# ws2811.net
KiCad netlist of a schematic drawn in EAGLE
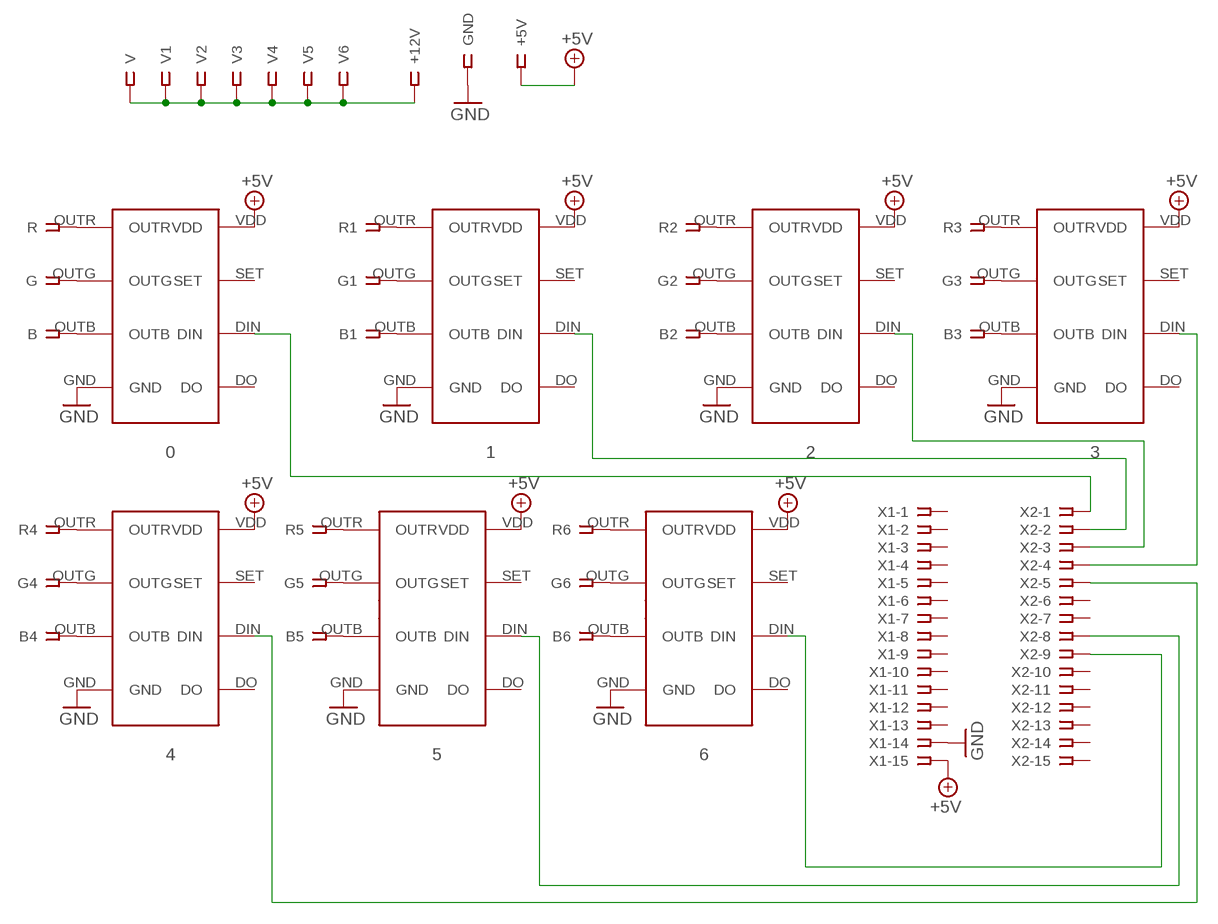
[diagram p0: schematic, sheet 1]

(export (version "E")
  (design (tool "Eeschema 10.0.6"))
  (components
    (comp (ref "+5V")
      (value "SSW-101-02-G-S")
      (footprint "eagle-import:SSW-101-02-G-S")
      (fields (field (name "MF") "Samtec Inc."))
      (libsource (lib "eagle-import") (part "SSW-101-02-G-S"))
    )
    (comp (ref "+12V")
      (value "SSW-101-02-G-S")
      (footprint "eagle-import:SSW-101-02-G-S")
      (fields (field (name "MF") "Samtec Inc."))
      (libsource (lib "eagle-import") (part "SSW-101-02-G-S"))
    )
    (comp (ref "0")
      (value "WS2811")
      (footprint "eagle-import:SOP8")
      (libsource (lib "eagle-import") (part "WS2811"))
    )
    (comp (ref "1")
      (value "WS2811")
      (footprint "eagle-import:SOP8")
      (libsource (lib "eagle-import") (part "WS2811"))
    )
    (comp (ref "2")
      (value "WS2811")
      (footprint "eagle-import:SOP8")
      (libsource (lib "eagle-import") (part "WS2811"))
    )
    (comp (ref "3")
      (value "WS2811")
      (footprint "eagle-import:SOP8")
      (libsource (lib "eagle-import") (part "WS2811"))
    )
    (comp (ref "4")
      (value "WS2811")
      (footprint "eagle-import:SOP8")
      (libsource (lib "eagle-import") (part "WS2811"))
    )
    (comp (ref "5")
      (value "WS2811")
      (footprint "eagle-import:SOP8")
      (libsource (lib "eagle-import") (part "WS2811"))
    )
    (comp (ref "6")
      (value "WS2811")
      (footprint "eagle-import:SOP8")
      (libsource (lib "eagle-import") (part "WS2811"))
    )
    (comp (ref "B")
      (value "SSW-101-02-G-S")
      (footprint "eagle-import:SSW-101-02-G-S")
      (fields (field (name "MF") "Samtec Inc."))
      (libsource (lib "eagle-import") (part "SSW-101-02-G-S"))
    )
    (comp (ref "B1")
      (value "SSW-101-02-G-S")
      (footprint "eagle-import:SSW-101-02-G-S")
      (fields (field (name "MF") "Samtec Inc."))
      (libsource (lib "eagle-import") (part "SSW-101-02-G-S"))
    )
    (comp (ref "B2")
      (value "SSW-101-02-G-S")
      (footprint "eagle-import:SSW-101-02-G-S")
      (fields (field (name "MF") "Samtec Inc."))
      (libsource (lib "eagle-import") (part "SSW-101-02-G-S"))
    )
    (comp (ref "B3")
      (value "SSW-101-02-G-S")
      (footprint "eagle-import:SSW-101-02-G-S")
      (fields (field (name "MF") "Samtec Inc."))
      (libsource (lib "eagle-import") (part "SSW-101-02-G-S"))
    )
    (comp (ref "B4")
      (value "SSW-101-02-G-S")
      (footprint "eagle-import:SSW-101-02-G-S")
      (fields (field (name "MF") "Samtec Inc."))
      (libsource (lib "eagle-import") (part "SSW-101-02-G-S"))
    )
    (comp (ref "B5")
      (value "SSW-101-02-G-S")
      (footprint "eagle-import:SSW-101-02-G-S")
      (fields (field (name "MF") "Samtec Inc."))
      (libsource (lib "eagle-import") (part "SSW-101-02-G-S"))
    )
    (comp (ref "B6")
      (value "SSW-101-02-G-S")
      (footprint "eagle-import:SSW-101-02-G-S")
      (fields (field (name "MF") "Samtec Inc."))
      (libsource (lib "eagle-import") (part "SSW-101-02-G-S"))
    )
    (comp (ref "G")
      (value "SSW-101-02-G-S")
      (footprint "eagle-import:SSW-101-02-G-S")
      (fields (field (name "MF") "Samtec Inc."))
      (libsource (lib "eagle-import") (part "SSW-101-02-G-S"))
    )
    (comp (ref "G1")
      (value "SSW-101-02-G-S")
      (footprint "eagle-import:SSW-101-02-G-S")
      (fields (field (name "MF") "Samtec Inc."))
      (libsource (lib "eagle-import") (part "SSW-101-02-G-S"))
    )
    (comp (ref "G2")
      (value "SSW-101-02-G-S")
      (footprint "eagle-import:SSW-101-02-G-S")
      (fields (field (name "MF") "Samtec Inc."))
      (libsource (lib "eagle-import") (part "SSW-101-02-G-S"))
    )
    (comp (ref "G3")
      (value "SSW-101-02-G-S")
      (footprint "eagle-import:SSW-101-02-G-S")
      (fields (field (name "MF") "Samtec Inc."))
      (libsource (lib "eagle-import") (part "SSW-101-02-G-S"))
    )
    (comp (ref "G4")
      (value "SSW-101-02-G-S")
      (footprint "eagle-import:SSW-101-02-G-S")
      (fields (field (name "MF") "Samtec Inc."))
      (libsource (lib "eagle-import") (part "SSW-101-02-G-S"))
    )
    (comp (ref "G5")
      (value "SSW-101-02-G-S")
      (footprint "eagle-import:SSW-101-02-G-S")
      (fields (field (name "MF") "Samtec Inc."))
      (libsource (lib "eagle-import") (part "SSW-101-02-G-S"))
    )
    (comp (ref "G6")
      (value "SSW-101-02-G-S")
      (footprint "eagle-import:SSW-101-02-G-S")
      (fields (field (name "MF") "Samtec Inc."))
      (libsource (lib "eagle-import") (part "SSW-101-02-G-S"))
    )
    (comp (ref "GND")
      (value "SSW-101-02-G-S")
      (footprint "eagle-import:SSW-101-02-G-S")
      (fields (field (name "MF") "Samtec Inc."))
      (libsource (lib "eagle-import") (part "SSW-101-02-G-S"))
    )
    (comp (ref "R")
      (value "SSW-101-02-G-S")
      (footprint "eagle-import:SSW-101-02-G-S")
      (fields (field (name "MF") "Samtec Inc."))
      (libsource (lib "eagle-import") (part "SSW-101-02-G-S"))
    )
    (comp (ref "R1")
      (value "SSW-101-02-G-S")
      (footprint "eagle-import:SSW-101-02-G-S")
      (fields (field (name "MF") "Samtec Inc."))
      (libsource (lib "eagle-import") (part "SSW-101-02-G-S"))
    )
    (comp (ref "R2")
      (value "SSW-101-02-G-S")
      (footprint "eagle-import:SSW-101-02-G-S")
      (fields (field (name "MF") "Samtec Inc."))
      (libsource (lib "eagle-import") (part "SSW-101-02-G-S"))
    )
    (comp (ref "R3")
      (value "SSW-101-02-G-S")
      (footprint "eagle-import:SSW-101-02-G-S")
      (fields (field (name "MF") "Samtec Inc."))
      (libsource (lib "eagle-import") (part "SSW-101-02-G-S"))
    )
    (comp (ref "R4")
      (value "SSW-101-02-G-S")
      (footprint "eagle-import:SSW-101-02-G-S")
      (fields (field (name "MF") "Samtec Inc."))
      (libsource (lib "eagle-import") (part "SSW-101-02-G-S"))
    )
    (comp (ref "R5")
      (value "SSW-101-02-G-S")
      (footprint "eagle-import:SSW-101-02-G-S")
      (fields (field (name "MF") "Samtec Inc."))
      (libsource (lib "eagle-import") (part "SSW-101-02-G-S"))
    )
    (comp (ref "R6")
      (value "SSW-101-02-G-S")
      (footprint "eagle-import:SSW-101-02-G-S")
      (fields (field (name "MF") "Samtec Inc."))
      (libsource (lib "eagle-import") (part "SSW-101-02-G-S"))
    )
    (comp (ref "V")
      (value "SSW-101-02-G-S")
      (footprint "eagle-import:SSW-101-02-G-S")
      (fields (field (name "MF") "Samtec Inc."))
      (libsource (lib "eagle-import") (part "SSW-101-02-G-S"))
    )
    (comp (ref "V1")
      (value "SSW-101-02-G-S")
      (footprint "eagle-import:SSW-101-02-G-S")
      (fields (field (name "MF") "Samtec Inc."))
      (libsource (lib "eagle-import") (part "SSW-101-02-G-S"))
    )
    (comp (ref "V2")
      (value "SSW-101-02-G-S")
      (footprint "eagle-import:SSW-101-02-G-S")
      (fields (field (name "MF") "Samtec Inc."))
      (libsource (lib "eagle-import") (part "SSW-101-02-G-S"))
    )
    (comp (ref "V3")
      (value "SSW-101-02-G-S")
      (footprint "eagle-import:SSW-101-02-G-S")
      (fields (field (name "MF") "Samtec Inc."))
      (libsource (lib "eagle-import") (part "SSW-101-02-G-S"))
    )
    (comp (ref "V4")
      (value "SSW-101-02-G-S")
      (footprint "eagle-import:SSW-101-02-G-S")
      (fields (field (name "MF") "Samtec Inc."))
      (libsource (lib "eagle-import") (part "SSW-101-02-G-S"))
    )
    (comp (ref "V5")
      (value "SSW-101-02-G-S")
      (footprint "eagle-import:SSW-101-02-G-S")
      (fields (field (name "MF") "Samtec Inc."))
      (libsource (lib "eagle-import") (part "SSW-101-02-G-S"))
    )
    (comp (ref "V6")
      (value "SSW-101-02-G-S")
      (footprint "eagle-import:SSW-101-02-G-S")
      (fields (field (name "MF") "Samtec Inc."))
      (libsource (lib "eagle-import") (part "SSW-101-02-G-S"))
    )
    (comp (ref "X1")
      (value "SSW-115-02-G-S")
      (footprint "eagle-import:SSW-115-02-G-S")
      (fields (field (name "MF") "Samtec Inc."))
      (libsource (lib "eagle-import") (part "SSW-115-02-G-S"))
    )
    (comp (ref "X2")
      (value "SSW-115-02-G-S")
      (footprint "eagle-import:SSW-115-02-G-S")
      (fields (field (name "MF") "Samtec Inc."))
      (libsource (lib "eagle-import") (part "SSW-115-02-G-S"))
    )
  )
  (nets
    (net (code "1") (name "+5V") (class "Default")
      (node (ref "+5V") (pin "1") (pinfunction "1_1") (pintype "passive"))
      (node (ref "0") (pin "VDD") (pinfunction "VDD_VDD") (pintype "bidirectional"))
      (node (ref "1") (pin "VDD") (pinfunction "VDD_VDD") (pintype "bidirectional"))
      (node (ref "2") (pin "VDD") (pinfunction "VDD_VDD") (pintype "bidirectional"))
      (node (ref "3") (pin "VDD") (pinfunction "VDD_VDD") (pintype "bidirectional"))
      (node (ref "4") (pin "VDD") (pinfunction "VDD_VDD") (pintype "bidirectional"))
      (node (ref "5") (pin "VDD") (pinfunction "VDD_VDD") (pintype "bidirectional"))
      (node (ref "6") (pin "VDD") (pinfunction "VDD_VDD") (pintype "bidirectional"))
      (node (ref "X1") (pin "15") (pinfunction "1_15") (pintype "passive"))
    )
    (net (code "2") (name "GND") (class "Default")
      (node (ref "0") (pin "GND") (pinfunction "GND_GND") (pintype "bidirectional"))
      (node (ref "1") (pin "GND") (pinfunction "GND_GND") (pintype "bidirectional"))
      (node (ref "2") (pin "GND") (pinfunction "GND_GND") (pintype "bidirectional"))
      (node (ref "3") (pin "GND") (pinfunction "GND_GND") (pintype "bidirectional"))
      (node (ref "4") (pin "GND") (pinfunction "GND_GND") (pintype "bidirectional"))
      (node (ref "5") (pin "GND") (pinfunction "GND_GND") (pintype "bidirectional"))
      (node (ref "6") (pin "GND") (pinfunction "GND_GND") (pintype "bidirectional"))
      (node (ref "GND") (pin "1") (pinfunction "1_1") (pintype "passive"))
      (node (ref "X1") (pin "14") (pinfunction "1_14") (pintype "passive"))
    )
    (net (code "3") (name "Net-(+12V-Pad1)") (class "Default")
      (node (ref "+12V") (pin "1") (pinfunction "1_1") (pintype "passive"))
      (node (ref "V") (pin "1") (pinfunction "1_1") (pintype "passive"))
      (node (ref "V1") (pin "1") (pinfunction "1_1") (pintype "passive"))
      (node (ref "V2") (pin "1") (pinfunction "1_1") (pintype "passive"))
      (node (ref "V3") (pin "1") (pinfunction "1_1") (pintype "passive"))
      (node (ref "V4") (pin "1") (pinfunction "1_1") (pintype "passive"))
      (node (ref "V5") (pin "1") (pinfunction "1_1") (pintype "passive"))
      (node (ref "V6") (pin "1") (pinfunction "1_1") (pintype "passive"))
    )
    (net (code "4") (name "Net-(0-PadDIN)") (class "Default")
      (node (ref "0") (pin "DIN") (pinfunction "DIN_DIN") (pintype "bidirectional"))
      (node (ref "X2") (pin "1") (pinfunction "1_1") (pintype "passive"))
    )
    (net (code "5") (name "Net-(0-PadOUTB)") (class "Default")
      (node (ref "0") (pin "OUTB") (pinfunction "OUTB_OUTB") (pintype "bidirectional"))
      (node (ref "B") (pin "1") (pinfunction "1_1") (pintype "passive"))
    )
    (net (code "6") (name "Net-(0-PadOUTG)") (class "Default")
      (node (ref "0") (pin "OUTG") (pinfunction "OUTG_OUTG") (pintype "bidirectional"))
      (node (ref "G") (pin "1") (pinfunction "1_1") (pintype "passive"))
    )
    (net (code "7") (name "Net-(0-PadOUTR)") (class "Default")
      (node (ref "0") (pin "OUTR") (pinfunction "OUTR_OUTR") (pintype "bidirectional"))
      (node (ref "R") (pin "1") (pinfunction "1_1") (pintype "passive"))
    )
    (net (code "8") (name "Net-(1-PadOUTB)") (class "Default")
      (node (ref "1") (pin "OUTB") (pinfunction "OUTB_OUTB") (pintype "bidirectional"))
      (node (ref "B1") (pin "1") (pinfunction "1_1") (pintype "passive"))
    )
    (net (code "9") (name "Net-(1-PadOUTG)") (class "Default")
      (node (ref "1") (pin "OUTG") (pinfunction "OUTG_OUTG") (pintype "bidirectional"))
      (node (ref "G1") (pin "1") (pinfunction "1_1") (pintype "passive"))
    )
    (net (code "10") (name "Net-(1-PadOUTR)") (class "Default")
      (node (ref "1") (pin "OUTR") (pinfunction "OUTR_OUTR") (pintype "bidirectional"))
      (node (ref "R1") (pin "1") (pinfunction "1_1") (pintype "passive"))
    )
    (net (code "11") (name "Net-(2-PadOUTB)") (class "Default")
      (node (ref "2") (pin "OUTB") (pinfunction "OUTB_OUTB") (pintype "bidirectional"))
      (node (ref "B2") (pin "1") (pinfunction "1_1") (pintype "passive"))
    )
    (net (code "12") (name "Net-(2-PadOUTG)") (class "Default")
      (node (ref "2") (pin "OUTG") (pinfunction "OUTG_OUTG") (pintype "bidirectional"))
      (node (ref "G2") (pin "1") (pinfunction "1_1") (pintype "passive"))
    )
    (net (code "13") (name "Net-(2-PadOUTR)") (class "Default")
      (node (ref "2") (pin "OUTR") (pinfunction "OUTR_OUTR") (pintype "bidirectional"))
      (node (ref "R2") (pin "1") (pinfunction "1_1") (pintype "passive"))
    )
    (net (code "14") (name "Net-(3-PadOUTB)") (class "Default")
      (node (ref "3") (pin "OUTB") (pinfunction "OUTB_OUTB") (pintype "bidirectional"))
      (node (ref "B3") (pin "1") (pinfunction "1_1") (pintype "passive"))
    )
    (net (code "15") (name "Net-(3-PadOUTG)") (class "Default")
      (node (ref "3") (pin "OUTG") (pinfunction "OUTG_OUTG") (pintype "bidirectional"))
      (node (ref "G3") (pin "1") (pinfunction "1_1") (pintype "passive"))
    )
    (net (code "16") (name "Net-(3-PadOUTR)") (class "Default")
      (node (ref "3") (pin "OUTR") (pinfunction "OUTR_OUTR") (pintype "bidirectional"))
      (node (ref "R3") (pin "1") (pinfunction "1_1") (pintype "passive"))
    )
    (net (code "17") (name "Net-(4-PadOUTB)") (class "Default")
      (node (ref "4") (pin "OUTB") (pinfunction "OUTB_OUTB") (pintype "bidirectional"))
      (node (ref "B4") (pin "1") (pinfunction "1_1") (pintype "passive"))
    )
    (net (code "18") (name "Net-(4-PadOUTG)") (class "Default")
      (node (ref "4") (pin "OUTG") (pinfunction "OUTG_OUTG") (pintype "bidirectional"))
      (node (ref "G4") (pin "1") (pinfunction "1_1") (pintype "passive"))
    )
    (net (code "19") (name "Net-(4-PadOUTR)") (class "Default")
      (node (ref "4") (pin "OUTR") (pinfunction "OUTR_OUTR") (pintype "bidirectional"))
      (node (ref "R4") (pin "1") (pinfunction "1_1") (pintype "passive"))
    )
    (net (code "20") (name "Net-(5-PadOUTB)") (class "Default")
      (node (ref "5") (pin "OUTB") (pinfunction "OUTB_OUTB") (pintype "bidirectional"))
      (node (ref "B5") (pin "1") (pinfunction "1_1") (pintype "passive"))
    )
    (net (code "21") (name "Net-(5-PadOUTG)") (class "Default")
      (node (ref "5") (pin "OUTG") (pinfunction "OUTG_OUTG") (pintype "bidirectional"))
      (node (ref "G5") (pin "1") (pinfunction "1_1") (pintype "passive"))
    )
    (net (code "22") (name "Net-(5-PadOUTR)") (class "Default")
      (node (ref "5") (pin "OUTR") (pinfunction "OUTR_OUTR") (pintype "bidirectional"))
      (node (ref "R5") (pin "1") (pinfunction "1_1") (pintype "passive"))
    )
    (net (code "23") (name "Net-(6-PadOUTB)") (class "Default")
      (node (ref "6") (pin "OUTB") (pinfunction "OUTB_OUTB") (pintype "bidirectional"))
      (node (ref "B6") (pin "1") (pinfunction "1_1") (pintype "passive"))
    )
    (net (code "24") (name "Net-(6-PadOUTG)") (class "Default")
      (node (ref "6") (pin "OUTG") (pinfunction "OUTG_OUTG") (pintype "bidirectional"))
      (node (ref "G6") (pin "1") (pinfunction "1_1") (pintype "passive"))
    )
    (net (code "25") (name "Net-(6-PadOUTR)") (class "Default")
      (node (ref "6") (pin "OUTR") (pinfunction "OUTR_OUTR") (pintype "bidirectional"))
      (node (ref "R6") (pin "1") (pinfunction "1_1") (pintype "passive"))
    )
    (net (code "26") (name "Net-(X2H-1)") (class "Default")
      (node (ref "1") (pin "DIN") (pinfunction "DIN_DIN") (pintype "bidirectional"))
      (node (ref "X2") (pin "2") (pinfunction "1_2") (pintype "passive"))
    )
    (net (code "27") (name "Net-(X2I-1)") (class "Default")
      (node (ref "2") (pin "DIN") (pinfunction "DIN_DIN") (pintype "bidirectional"))
      (node (ref "X2") (pin "3") (pinfunction "1_3") (pintype "passive"))
    )
    (net (code "28") (name "Net-(X2J-1)") (class "Default")
      (node (ref "3") (pin "DIN") (pinfunction "DIN_DIN") (pintype "bidirectional"))
      (node (ref "X2") (pin "4") (pinfunction "1_4") (pintype "passive"))
    )
    (net (code "29") (name "Net-(X2K-1)") (class "Default")
      (node (ref "4") (pin "DIN") (pinfunction "DIN_DIN") (pintype "bidirectional"))
      (node (ref "X2") (pin "5") (pinfunction "1_5") (pintype "passive"))
    )
    (net (code "30") (name "Net-(X2N-1)") (class "Default")
      (node (ref "5") (pin "DIN") (pinfunction "DIN_DIN") (pintype "bidirectional"))
      (node (ref "X2") (pin "8") (pinfunction "1_8") (pintype "passive"))
    )
    (net (code "31") (name "Net-(X2O-1)") (class "Default")
      (node (ref "6") (pin "DIN") (pinfunction "DIN_DIN") (pintype "bidirectional"))
      (node (ref "X2") (pin "9") (pinfunction "1_9") (pintype "passive"))
    )
    (net (code "32") (name "unconnected-(0-PadDO)") (class "Default")
      (node (ref "0") (pin "DO") (pinfunction "DO_DO") (pintype "bidirectional"))
    )
    (net (code "33") (name "unconnected-(0-PadSET)") (class "Default")
      (node (ref "0") (pin "SET") (pinfunction "SET_SET") (pintype "bidirectional"))
    )
    (net (code "34") (name "unconnected-(1-PadDO)") (class "Default")
      (node (ref "1") (pin "DO") (pinfunction "DO_DO") (pintype "bidirectional"))
    )
    (net (code "35") (name "unconnected-(1-PadSET)") (class "Default")
      (node (ref "1") (pin "SET") (pinfunction "SET_SET") (pintype "bidirectional"))
    )
    (net (code "36") (name "unconnected-(2-PadDO)") (class "Default")
      (node (ref "2") (pin "DO") (pinfunction "DO_DO") (pintype "bidirectional"))
    )
    (net (code "37") (name "unconnected-(2-PadSET)") (class "Default")
      (node (ref "2") (pin "SET") (pinfunction "SET_SET") (pintype "bidirectional"))
    )
    (net (code "38") (name "unconnected-(3-PadDO)") (class "Default")
      (node (ref "3") (pin "DO") (pinfunction "DO_DO") (pintype "bidirectional"))
    )
    (net (code "39") (name "unconnected-(3-PadSET)") (class "Default")
      (node (ref "3") (pin "SET") (pinfunction "SET_SET") (pintype "bidirectional"))
    )
    (net (code "40") (name "unconnected-(4-PadDO)") (class "Default")
      (node (ref "4") (pin "DO") (pinfunction "DO_DO") (pintype "bidirectional"))
    )
    (net (code "41") (name "unconnected-(4-PadSET)") (class "Default")
      (node (ref "4") (pin "SET") (pinfunction "SET_SET") (pintype "bidirectional"))
    )
    (net (code "42") (name "unconnected-(5-PadDO)") (class "Default")
      (node (ref "5") (pin "DO") (pinfunction "DO_DO") (pintype "bidirectional"))
    )
    (net (code "43") (name "unconnected-(5-PadSET)") (class "Default")
      (node (ref "5") (pin "SET") (pinfunction "SET_SET") (pintype "bidirectional"))
    )
    (net (code "44") (name "unconnected-(6-PadDO)") (class "Default")
      (node (ref "6") (pin "DO") (pinfunction "DO_DO") (pintype "bidirectional"))
    )
    (net (code "45") (name "unconnected-(6-PadSET)") (class "Default")
      (node (ref "6") (pin "SET") (pinfunction "SET_SET") (pintype "bidirectional"))
    )
    (net (code "46") (name "unconnected-(X1-Pad1)") (class "Default")
      (node (ref "X1") (pin "1") (pinfunction "1_1") (pintype "passive"))
    )
    (net (code "47") (name "unconnected-(X1B-1-Pad10)") (class "Default")
      (node (ref "X1") (pin "10") (pinfunction "1_10") (pintype "passive"))
    )
    (net (code "48") (name "unconnected-(X1C-1-Pad11)") (class "Default")
      (node (ref "X1") (pin "11") (pinfunction "1_11") (pintype "passive"))
    )
    (net (code "49") (name "unconnected-(X1D-1-Pad12)") (class "Default")
      (node (ref "X1") (pin "12") (pinfunction "1_12") (pintype "passive"))
    )
    (net (code "50") (name "unconnected-(X1E-1-Pad13)") (class "Default")
      (node (ref "X1") (pin "13") (pinfunction "1_13") (pintype "passive"))
    )
    (net (code "51") (name "unconnected-(X1H-1-Pad2)") (class "Default")
      (node (ref "X1") (pin "2") (pinfunction "1_2") (pintype "passive"))
    )
    (net (code "52") (name "unconnected-(X1I-1-Pad3)") (class "Default")
      (node (ref "X1") (pin "3") (pinfunction "1_3") (pintype "passive"))
    )
    (net (code "53") (name "unconnected-(X1J-1-Pad4)") (class "Default")
      (node (ref "X1") (pin "4") (pinfunction "1_4") (pintype "passive"))
    )
    (net (code "54") (name "unconnected-(X1K-1-Pad5)") (class "Default")
      (node (ref "X1") (pin "5") (pinfunction "1_5") (pintype "passive"))
    )
    (net (code "55") (name "unconnected-(X1L-1-Pad6)") (class "Default")
      (node (ref "X1") (pin "6") (pinfunction "1_6") (pintype "passive"))
    )
    (net (code "56") (name "unconnected-(X1M-1-Pad7)") (class "Default")
      (node (ref "X1") (pin "7") (pinfunction "1_7") (pintype "passive"))
    )
    (net (code "57") (name "unconnected-(X1N-1-Pad8)") (class "Default")
      (node (ref "X1") (pin "8") (pinfunction "1_8") (pintype "passive"))
    )
    (net (code "58") (name "unconnected-(X1O-1-Pad9)") (class "Default")
      (node (ref "X1") (pin "9") (pinfunction "1_9") (pintype "passive"))
    )
    (net (code "59") (name "unconnected-(X2B-1-Pad10)") (class "Default")
      (node (ref "X2") (pin "10") (pinfunction "1_10") (pintype "passive"))
    )
    (net (code "60") (name "unconnected-(X2C-1-Pad11)") (class "Default")
      (node (ref "X2") (pin "11") (pinfunction "1_11") (pintype "passive"))
    )
    (net (code "61") (name "unconnected-(X2D-1-Pad12)") (class "Default")
      (node (ref "X2") (pin "12") (pinfunction "1_12") (pintype "passive"))
    )
    (net (code "62") (name "unconnected-(X2E-1-Pad13)") (class "Default")
      (node (ref "X2") (pin "13") (pinfunction "1_13") (pintype "passive"))
    )
    (net (code "63") (name "unconnected-(X2F-1-Pad14)") (class "Default")
      (node (ref "X2") (pin "14") (pinfunction "1_14") (pintype "passive"))
    )
    (net (code "64") (name "unconnected-(X2G-1-Pad15)") (class "Default")
      (node (ref "X2") (pin "15") (pinfunction "1_15") (pintype "passive"))
    )
    (net (code "65") (name "unconnected-(X2L-1-Pad6)") (class "Default")
      (node (ref "X2") (pin "6") (pinfunction "1_6") (pintype "passive"))
    )
    (net (code "66") (name "unconnected-(X2M-1-Pad7)") (class "Default")
      (node (ref "X2") (pin "7") (pinfunction "1_7") (pintype "passive"))
    )
  )
)
